# main_schematic_8.net
KiCad netlist of a schematic drawn in EAGLE
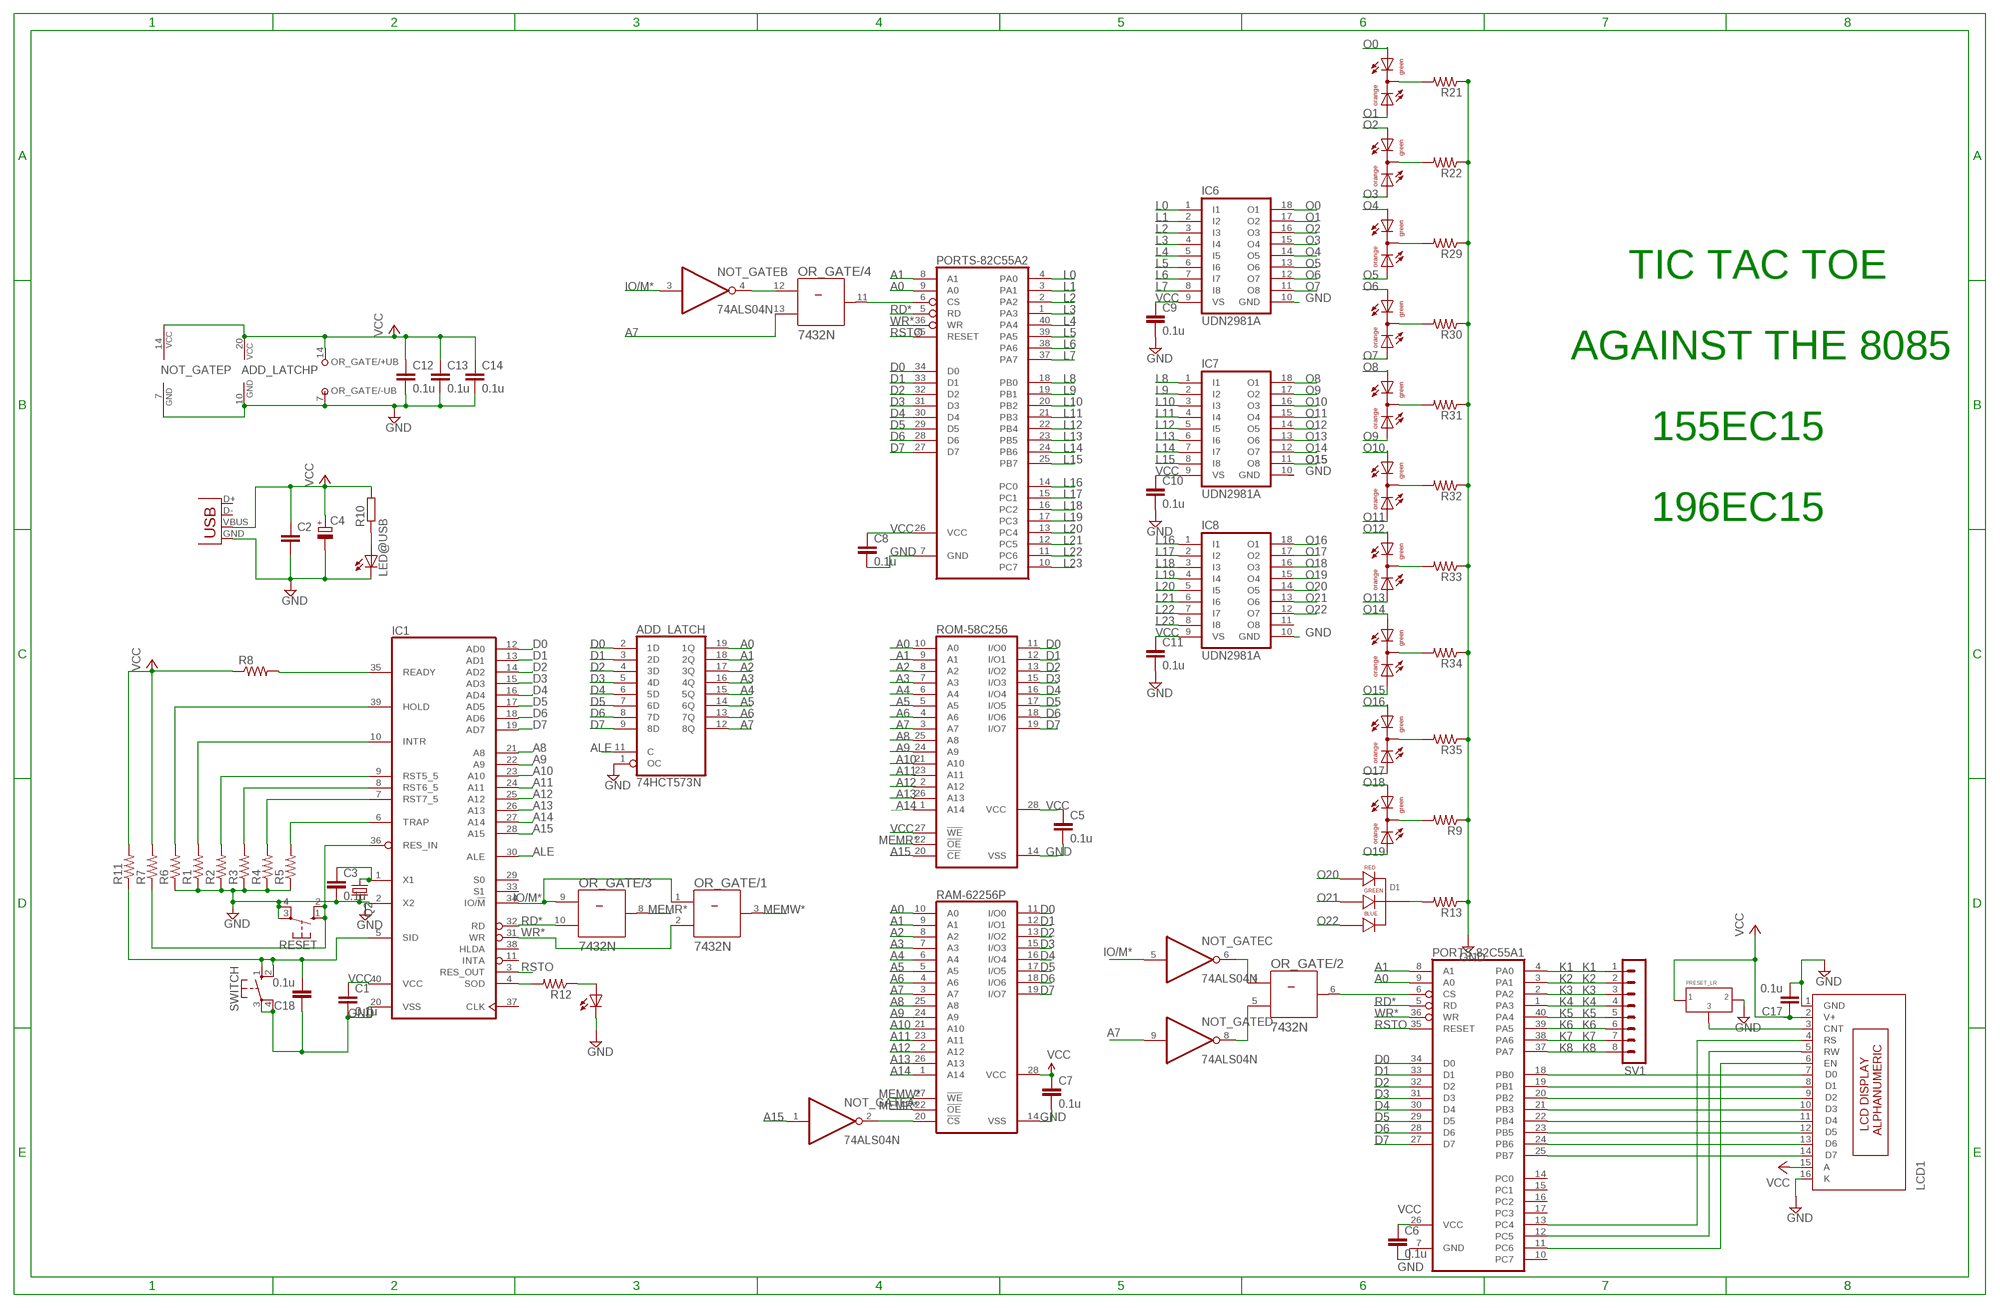
[diagram p0: schematic, sheet 1]

(export (version "E")
  (design (tool "Eeschema 10.0.6"))
  (components
    (comp (ref "ADD_LATCH")
      (value "74HCT573N")
      (footprint "eagle-import:DIL20")
      (libsource (lib "eagle-import") (part "74573NHCT"))
    )
    (comp (ref "C1")
      (value "0.1u")
      (footprint "eagle-import:C2.5-3")
      (libsource (lib "eagle-import") (part "capacitor-wima_116_C2,5-3"))
    )
    (comp (ref "C2")
      (value "C-EU025-024X044")
      (footprint "eagle-import:C025-024X044")
      (libsource (lib "eagle-import") (part "C-EU025-024X044"))
    )
    (comp (ref "C3")
      (value "0.1u")
      (footprint "eagle-import:C025-024X044")
      (libsource (lib "eagle-import") (part "C-EU025-024X044"))
    )
    (comp (ref "C4")
      (value "CPOL-EUE5-8.5")
      (footprint "eagle-import:E5-8,5")
      (libsource (lib "eagle-import") (part "CPOL-EUE5-8.5"))
    )
    (comp (ref "C5")
      (value "0.1u")
      (footprint "eagle-import:C025-024X044")
      (libsource (lib "eagle-import") (part "C-EU025-024X044"))
    )
    (comp (ref "C6")
      (value "0.1u")
      (footprint "eagle-import:C050-024X044")
      (libsource (lib "eagle-import") (part "resistor_C-EU050-024X044"))
    )
    (comp (ref "C7")
      (value "0.1u")
      (footprint "eagle-import:C025-024X044")
      (libsource (lib "eagle-import") (part "C-EU025-024X044"))
    )
    (comp (ref "C8")
      (value "0.1u")
      (footprint "eagle-import:C025-024X044")
      (libsource (lib "eagle-import") (part "C-EU025-024X044"))
    )
    (comp (ref "C9")
      (value "0.1u")
      (footprint "eagle-import:C025-024X044")
      (libsource (lib "eagle-import") (part "C-EU025-024X044"))
    )
    (comp (ref "C10")
      (value "0.1u")
      (footprint "eagle-import:C025-024X044")
      (libsource (lib "eagle-import") (part "C-EU025-024X044"))
    )
    (comp (ref "C11")
      (value "0.1u")
      (footprint "eagle-import:C025-024X044")
      (libsource (lib "eagle-import") (part "C-EU025-024X044"))
    )
    (comp (ref "C12")
      (value "0.1u")
      (footprint "eagle-import:C025-024X044")
      (libsource (lib "eagle-import") (part "C-EU025-024X044"))
    )
    (comp (ref "C13")
      (value "0.1u")
      (footprint "eagle-import:C025-024X044")
      (libsource (lib "eagle-import") (part "C-EU025-024X044"))
    )
    (comp (ref "C14")
      (value "0.1u")
      (footprint "eagle-import:C025-024X044")
      (libsource (lib "eagle-import") (part "C-EU025-024X044"))
    )
    (comp (ref "C17")
      (value "0.1u")
      (footprint "eagle-import:C025-024X044")
      (libsource (lib "eagle-import") (part "C-EU025-024X044"))
    )
    (comp (ref "C18")
      (value "0.1u")
      (footprint "eagle-import:C2.5-3")
      (libsource (lib "eagle-import") (part "C2,5-3"))
    )
    (comp (ref "D1")
      (value "LED-RGB-CC-THRUCLEAR")
      (footprint "eagle-import:LED-RGB-THRU")
      (libsource (lib "eagle-import") (part "LED-RGB-CC-THRUCLEAR"))
    )
    (comp (ref "IC1")
      (value "8085")
      (footprint "eagle-import:DIL40")
      (libsource (lib "eagle-import") (part "8085"))
    )
    (comp (ref "IC6")
      (value "UDN2981A")
      (footprint "eagle-import:DIL18")
      (libsource (lib "eagle-import") (part "UDN298A1"))
    )
    (comp (ref "IC7")
      (value "UDN2981A")
      (footprint "eagle-import:DIL18")
      (libsource (lib "eagle-import") (part "UDN298A1"))
    )
    (comp (ref "IC8")
      (value "UDN2981A")
      (footprint "eagle-import:DIL18")
      (libsource (lib "eagle-import") (part "UDN298A1"))
    )
    (comp (ref "LCD1")
      (value "16X2LCD")
      (footprint "eagle-import:16X2_LCD")
      (libsource (lib "eagle-import") (part "16X2LCD"))
    )
    (comp (ref "LED@SOD")
      (value "LED3MM")
      (footprint "eagle-import:LED3MM")
      (libsource (lib "eagle-import") (part "led_LED3MM"))
    )
    (comp (ref "LED@USB")
      (value "LED5MM")
      (footprint "eagle-import:LED5MM")
      (libsource (lib "eagle-import") (part "LED5MM"))
    )
    (comp (ref "LEDA")
      (value "TLUV5300")
      (footprint "eagle-import:TLUV5300")
      (libsource (lib "eagle-import") (part "TLUV5300"))
    )
    (comp (ref "LEDB")
      (value "TLUV5300")
      (footprint "eagle-import:TLUV5300")
      (libsource (lib "eagle-import") (part "TLUV5300"))
    )
    (comp (ref "LEDC")
      (value "TLUV5300")
      (footprint "eagle-import:TLUV5300")
      (libsource (lib "eagle-import") (part "TLUV5300"))
    )
    (comp (ref "LEDD")
      (value "TLUV5300")
      (footprint "eagle-import:TLUV5300")
      (libsource (lib "eagle-import") (part "TLUV5300"))
    )
    (comp (ref "LEDE")
      (value "TLUV5300")
      (footprint "eagle-import:TLUV5300")
      (libsource (lib "eagle-import") (part "TLUV5300"))
    )
    (comp (ref "LEDF")
      (value "TLUV5300")
      (footprint "eagle-import:TLUV5300")
      (libsource (lib "eagle-import") (part "TLUV5300"))
    )
    (comp (ref "LEDG")
      (value "TLUV5300")
      (footprint "eagle-import:TLUV5300")
      (libsource (lib "eagle-import") (part "TLUV5300"))
    )
    (comp (ref "LEDH")
      (value "TLUV5300")
      (footprint "eagle-import:TLUV5300")
      (libsource (lib "eagle-import") (part "TLUV5300"))
    )
    (comp (ref "LEDI")
      (value "TLUV5300")
      (footprint "eagle-import:TLUV5300")
      (libsource (lib "eagle-import") (part "TLUV5300"))
    )
    (comp (ref "LEDJ")
      (value "TLUV5300")
      (footprint "eagle-import:TLUV5300")
      (libsource (lib "eagle-import") (part "TLUV5300"))
    )
    (comp (ref "NOT_GATE")
      (value "74ALS04N")
      (footprint "eagle-import:DIL14")
      (libsource (lib "eagle-import") (part "7404NALS"))
    )
    (comp (ref "OR_GATE")
      (value "7432N")
      (footprint "eagle-import:DIL14")
      (fields (field (name "SPICEPREFIX") "J"))
      (libsource (lib "eagle-import") (part "7432N"))
    )
    (comp (ref "PORTS-82C55A1")
      (value "82C55A")
      (footprint "eagle-import:DIL40")
      (fields (field (name "MF") "INTERSIL") (field (name "MPN") "IP82C55AZ"))
      (libsource (lib "eagle-import") (part "82C55A"))
    )
    (comp (ref "PORTS-82C55A2")
      (value "82C55A")
      (footprint "eagle-import:DIL40")
      (fields (field (name "MF") "INTERSIL") (field (name "MPN") "IP82C55AZ"))
      (libsource (lib "eagle-import") (part "82C55A"))
    )
    (comp (ref "Q2")
      (value "CRYSTALHC49US")
      (footprint "eagle-import:HC49US")
      (libsource (lib "eagle-import") (part "CRYSTALHC49US"))
    )
    (comp (ref "R1")
      (value "R-US_0204/2V")
      (footprint "eagle-import:0204V")
      (libsource (lib "eagle-import") (part "R-US_0204/2V"))
    )
    (comp (ref "R2")
      (value "R-US_0204/2V")
      (footprint "eagle-import:0204V")
      (libsource (lib "eagle-import") (part "R-US_0204/2V"))
    )
    (comp (ref "R3")
      (value "R-US_0204/2V")
      (footprint "eagle-import:0204V")
      (libsource (lib "eagle-import") (part "R-US_0204/2V"))
    )
    (comp (ref "R4")
      (value "R-US_0204/2V")
      (footprint "eagle-import:0204V")
      (libsource (lib "eagle-import") (part "R-US_0204/2V"))
    )
    (comp (ref "R5")
      (value "R-US_0204/2V")
      (footprint "eagle-import:0204V")
      (libsource (lib "eagle-import") (part "R-US_0204/2V"))
    )
    (comp (ref "R6")
      (value "R-US_0204/2V")
      (footprint "eagle-import:0204V")
      (libsource (lib "eagle-import") (part "R-US_0204/2V"))
    )
    (comp (ref "R7")
      (value "R-US_0204/2V")
      (footprint "eagle-import:0204V")
      (libsource (lib "eagle-import") (part "R-US_0204/2V"))
    )
    (comp (ref "R8")
      (value "R-US_0204/2V")
      (footprint "eagle-import:0204V")
      (libsource (lib "eagle-import") (part "R-US_0204/2V"))
    )
    (comp (ref "R9")
      (value "R-US_0204/2V")
      (footprint "eagle-import:0204V")
      (libsource (lib "eagle-import") (part "R-US_0204/2V"))
    )
    (comp (ref "R10")
      (value "R-EU_0204/7")
      (footprint "eagle-import:0204_7")
      (libsource (lib "eagle-import") (part "R-EU_0204/7"))
    )
    (comp (ref "R11")
      (value "R-US_0204/2V")
      (footprint "eagle-import:0204V")
      (libsource (lib "eagle-import") (part "R-US_0204/2V"))
    )
    (comp (ref "R12")
      (value "R-US_0204/2V")
      (footprint "eagle-import:0204V")
      (libsource (lib "eagle-import") (part "R-US_0204/2V"))
    )
    (comp (ref "R13")
      (value "R-US_0204/2V")
      (footprint "eagle-import:0204V")
      (libsource (lib "eagle-import") (part "R-US_0204/2V"))
    )
    (comp (ref "R21")
      (value "R-US_0204/2V")
      (footprint "eagle-import:0204V")
      (libsource (lib "eagle-import") (part "R-US_0204/2V"))
    )
    (comp (ref "R22")
      (value "R-US_0204/2V")
      (footprint "eagle-import:0204V")
      (libsource (lib "eagle-import") (part "R-US_0204/2V"))
    )
    (comp (ref "R29")
      (value "R-US_0204/2V")
      (footprint "eagle-import:0204V")
      (libsource (lib "eagle-import") (part "R-US_0204/2V"))
    )
    (comp (ref "R30")
      (value "R-US_0204/2V")
      (footprint "eagle-import:0204V")
      (libsource (lib "eagle-import") (part "R-US_0204/2V"))
    )
    (comp (ref "R31")
      (value "R-US_0204/2V")
      (footprint "eagle-import:0204V")
      (libsource (lib "eagle-import") (part "R-US_0204/2V"))
    )
    (comp (ref "R32")
      (value "R-US_0204/2V")
      (footprint "eagle-import:0204V")
      (libsource (lib "eagle-import") (part "R-US_0204/2V"))
    )
    (comp (ref "R33")
      (value "R-US_0204/2V")
      (footprint "eagle-import:0204V")
      (libsource (lib "eagle-import") (part "R-US_0204/2V"))
    )
    (comp (ref "R34")
      (value "R-US_0204/2V")
      (footprint "eagle-import:0204V")
      (libsource (lib "eagle-import") (part "R-US_0204/2V"))
    )
    (comp (ref "R35")
      (value "R-US_0204/2V")
      (footprint "eagle-import:0204V")
      (libsource (lib "eagle-import") (part "R-US_0204/2V"))
    )
    (comp (ref "RAM-62256P")
      (value "62256P")
      (footprint "eagle-import:DIL28-6")
      (libsource (lib "eagle-import") (part "62256P"))
    )
    (comp (ref "RESET")
      (value "10-XX")
      (footprint "eagle-import:B3F-10XX")
      (libsource (lib "eagle-import") (part "10-XX"))
    )
    (comp (ref "ROM-58C256")
      (value "58C256P")
      (footprint "eagle-import:DIL28-6")
      (fields (field (name "MPN") "HN58C256AP85E"))
      (libsource (lib "eagle-import") (part "58C256P"))
    )
    (comp (ref "SV1")
      (value "MA08-1")
      (footprint "eagle-import:MA08-1")
      (libsource (lib "eagle-import") (part "MA08-1"))
    )
    (comp (ref "SWITCH")
      (value "10-XX")
      (footprint "eagle-import:B3F-10XX")
      (libsource (lib "eagle-import") (part "CEDTv69_10-XX"))
    )
    (comp (ref "U$2")
      (value "PRESET_LR")
      (footprint "eagle-import:PRESET_LR")
      (libsource (lib "eagle-import") (part "PRESET_LR"))
    )
    (comp (ref "X1")
      (value "USBSMD")
      (footprint "eagle-import:USB-MINIB")
      (libsource (lib "eagle-import") (part "USBSMD"))
    )
  )
  (nets
    (net (code "1") (name "/A0") (class "Default")
      (node (ref "ADD_LATCH") (pin "19") (pinfunction "1Q_19") (pintype "tri_state"))
      (node (ref "PORTS-82C55A1") (pin "9") (pinfunction "A0_9") (pintype "input"))
      (node (ref "PORTS-82C55A2") (pin "9") (pinfunction "A0_9") (pintype "input"))
      (node (ref "RAM-62256P") (pin "10") (pinfunction "A0_10") (pintype "input"))
      (node (ref "ROM-58C256") (pin "10") (pinfunction "A0_10") (pintype "input"))
    )
    (net (code "2") (name "/A1") (class "Default")
      (node (ref "ADD_LATCH") (pin "18") (pinfunction "2Q_18") (pintype "tri_state"))
      (node (ref "PORTS-82C55A1") (pin "8") (pinfunction "A1_8") (pintype "input"))
      (node (ref "PORTS-82C55A2") (pin "8") (pinfunction "A1_8") (pintype "input"))
      (node (ref "RAM-62256P") (pin "9") (pinfunction "A1_9") (pintype "input"))
      (node (ref "ROM-58C256") (pin "9") (pinfunction "A1_9") (pintype "input"))
    )
    (net (code "3") (name "/A2") (class "Default")
      (node (ref "ADD_LATCH") (pin "17") (pinfunction "3Q_17") (pintype "tri_state"))
      (node (ref "RAM-62256P") (pin "8") (pinfunction "A2_8") (pintype "input"))
      (node (ref "ROM-58C256") (pin "8") (pinfunction "A2_8") (pintype "input"))
    )
    (net (code "4") (name "/A3") (class "Default")
      (node (ref "ADD_LATCH") (pin "16") (pinfunction "4Q_16") (pintype "tri_state"))
      (node (ref "RAM-62256P") (pin "7") (pinfunction "A3_7") (pintype "input"))
      (node (ref "ROM-58C256") (pin "7") (pinfunction "A3_7") (pintype "input"))
    )
    (net (code "5") (name "/A4") (class "Default")
      (node (ref "ADD_LATCH") (pin "15") (pinfunction "5Q_15") (pintype "tri_state"))
      (node (ref "RAM-62256P") (pin "6") (pinfunction "A4_6") (pintype "input"))
      (node (ref "ROM-58C256") (pin "6") (pinfunction "A4_6") (pintype "input"))
    )
    (net (code "6") (name "/A5") (class "Default")
      (node (ref "ADD_LATCH") (pin "14") (pinfunction "6Q_14") (pintype "tri_state"))
      (node (ref "RAM-62256P") (pin "5") (pinfunction "A5_5") (pintype "input"))
      (node (ref "ROM-58C256") (pin "5") (pinfunction "A5_5") (pintype "input"))
    )
    (net (code "7") (name "/A6") (class "Default")
      (node (ref "ADD_LATCH") (pin "13") (pinfunction "7Q_13") (pintype "tri_state"))
      (node (ref "RAM-62256P") (pin "4") (pinfunction "A6_4") (pintype "input"))
      (node (ref "ROM-58C256") (pin "4") (pinfunction "A6_4") (pintype "input"))
    )
    (net (code "8") (name "/A7") (class "Default")
      (node (ref "ADD_LATCH") (pin "12") (pinfunction "8Q_12") (pintype "tri_state"))
      (node (ref "NOT_GATE") (pin "9") (pinfunction "I_9") (pintype "input"))
      (node (ref "OR_GATE") (pin "13") (pinfunction "B_13") (pintype "input"))
      (node (ref "RAM-62256P") (pin "3") (pinfunction "A7_3") (pintype "input"))
      (node (ref "ROM-58C256") (pin "3") (pinfunction "A7_3") (pintype "input"))
    )
    (net (code "9") (name "/A8") (class "Default")
      (node (ref "IC1") (pin "21") (pinfunction "A8_21") (pintype "output"))
      (node (ref "RAM-62256P") (pin "25") (pinfunction "A8_25") (pintype "input"))
      (node (ref "ROM-58C256") (pin "25") (pinfunction "A8_25") (pintype "input"))
    )
    (net (code "10") (name "/A9") (class "Default")
      (node (ref "IC1") (pin "22") (pinfunction "A9_22") (pintype "output"))
      (node (ref "RAM-62256P") (pin "24") (pinfunction "A9_24") (pintype "input"))
      (node (ref "ROM-58C256") (pin "24") (pinfunction "A9_24") (pintype "input"))
    )
    (net (code "11") (name "/A10") (class "Default")
      (node (ref "IC1") (pin "23") (pinfunction "A10_23") (pintype "output"))
      (node (ref "RAM-62256P") (pin "21") (pinfunction "A10_21") (pintype "input"))
      (node (ref "ROM-58C256") (pin "21") (pinfunction "A10_21") (pintype "input"))
    )
    (net (code "12") (name "/A11") (class "Default")
      (node (ref "IC1") (pin "24") (pinfunction "A11_24") (pintype "output"))
      (node (ref "RAM-62256P") (pin "23") (pinfunction "A11_23") (pintype "input"))
      (node (ref "ROM-58C256") (pin "23") (pinfunction "A11_23") (pintype "input"))
    )
    (net (code "13") (name "/A12") (class "Default")
      (node (ref "IC1") (pin "25") (pinfunction "A12_25") (pintype "output"))
      (node (ref "RAM-62256P") (pin "2") (pinfunction "A12_2") (pintype "input"))
      (node (ref "ROM-58C256") (pin "2") (pinfunction "A12_2") (pintype "input"))
    )
    (net (code "14") (name "/A13") (class "Default")
      (node (ref "IC1") (pin "26") (pinfunction "A13_26") (pintype "output"))
      (node (ref "RAM-62256P") (pin "26") (pinfunction "A13_26") (pintype "input"))
      (node (ref "ROM-58C256") (pin "26") (pinfunction "A13_26") (pintype "input"))
    )
    (net (code "15") (name "/A14") (class "Default")
      (node (ref "IC1") (pin "27") (pinfunction "A14_27") (pintype "output"))
      (node (ref "RAM-62256P") (pin "1") (pinfunction "A14_1") (pintype "input"))
      (node (ref "ROM-58C256") (pin "1") (pinfunction "A14_1") (pintype "input"))
    )
    (net (code "16") (name "/A15") (class "Default")
      (node (ref "IC1") (pin "28") (pinfunction "A15_28") (pintype "output"))
      (node (ref "NOT_GATE") (pin "1") (pinfunction "I_1") (pintype "input"))
      (node (ref "ROM-58C256") (pin "20") (pinfunction "~{CE}_20") (pintype "input"))
    )
    (net (code "17") (name "/ALE") (class "Default")
      (node (ref "ADD_LATCH") (pin "11") (pinfunction "C_11") (pintype "input"))
      (node (ref "IC1") (pin "30") (pinfunction "ALE_30") (pintype "output"))
    )
    (net (code "18") (name "/D0") (class "Default")
      (node (ref "ADD_LATCH") (pin "2") (pinfunction "1D_2") (pintype "input"))
      (node (ref "IC1") (pin "12") (pinfunction "AD0_12") (pintype "bidirectional"))
      (node (ref "PORTS-82C55A1") (pin "34") (pinfunction "D0_34") (pintype "bidirectional"))
      (node (ref "PORTS-82C55A2") (pin "34") (pinfunction "D0_34") (pintype "bidirectional"))
      (node (ref "RAM-62256P") (pin "11") (pinfunction "I/O0_11") (pintype "bidirectional"))
      (node (ref "ROM-58C256") (pin "11") (pinfunction "I/O0_11") (pintype "tri_state"))
    )
    (net (code "19") (name "/D1") (class "Default")
      (node (ref "ADD_LATCH") (pin "3") (pinfunction "2D_3") (pintype "input"))
      (node (ref "IC1") (pin "13") (pinfunction "AD1_13") (pintype "bidirectional"))
      (node (ref "PORTS-82C55A1") (pin "33") (pinfunction "D1_33") (pintype "bidirectional"))
      (node (ref "PORTS-82C55A2") (pin "33") (pinfunction "D1_33") (pintype "bidirectional"))
      (node (ref "RAM-62256P") (pin "12") (pinfunction "I/O1_12") (pintype "bidirectional"))
      (node (ref "ROM-58C256") (pin "12") (pinfunction "I/O1_12") (pintype "tri_state"))
    )
    (net (code "20") (name "/D2") (class "Default")
      (node (ref "ADD_LATCH") (pin "4") (pinfunction "3D_4") (pintype "input"))
      (node (ref "IC1") (pin "14") (pinfunction "AD2_14") (pintype "bidirectional"))
      (node (ref "PORTS-82C55A1") (pin "32") (pinfunction "D2_32") (pintype "bidirectional"))
      (node (ref "PORTS-82C55A2") (pin "32") (pinfunction "D2_32") (pintype "bidirectional"))
      (node (ref "RAM-62256P") (pin "13") (pinfunction "I/O2_13") (pintype "bidirectional"))
      (node (ref "ROM-58C256") (pin "13") (pinfunction "I/O2_13") (pintype "tri_state"))
    )
    (net (code "21") (name "/D3") (class "Default")
      (node (ref "ADD_LATCH") (pin "5") (pinfunction "4D_5") (pintype "input"))
      (node (ref "IC1") (pin "15") (pinfunction "AD3_15") (pintype "bidirectional"))
      (node (ref "PORTS-82C55A1") (pin "31") (pinfunction "D3_31") (pintype "bidirectional"))
      (node (ref "PORTS-82C55A2") (pin "31") (pinfunction "D3_31") (pintype "bidirectional"))
      (node (ref "RAM-62256P") (pin "15") (pinfunction "I/O3_15") (pintype "bidirectional"))
      (node (ref "ROM-58C256") (pin "15") (pinfunction "I/O3_15") (pintype "tri_state"))
    )
    (net (code "22") (name "/D4") (class "Default")
      (node (ref "ADD_LATCH") (pin "6") (pinfunction "5D_6") (pintype "input"))
      (node (ref "IC1") (pin "16") (pinfunction "AD4_16") (pintype "bidirectional"))
      (node (ref "PORTS-82C55A1") (pin "30") (pinfunction "D4_30") (pintype "bidirectional"))
      (node (ref "PORTS-82C55A2") (pin "30") (pinfunction "D4_30") (pintype "bidirectional"))
      (node (ref "RAM-62256P") (pin "16") (pinfunction "I/O4_16") (pintype "bidirectional"))
      (node (ref "ROM-58C256") (pin "16") (pinfunction "I/O4_16") (pintype "tri_state"))
    )
    (net (code "23") (name "/D5") (class "Default")
      (node (ref "ADD_LATCH") (pin "7") (pinfunction "6D_7") (pintype "input"))
      (node (ref "IC1") (pin "17") (pinfunction "AD5_17") (pintype "bidirectional"))
      (node (ref "PORTS-82C55A1") (pin "29") (pinfunction "D5_29") (pintype "bidirectional"))
      (node (ref "PORTS-82C55A2") (pin "29") (pinfunction "D5_29") (pintype "bidirectional"))
      (node (ref "RAM-62256P") (pin "17") (pinfunction "I/O5_17") (pintype "bidirectional"))
      (node (ref "ROM-58C256") (pin "17") (pinfunction "I/O5_17") (pintype "tri_state"))
    )
    (net (code "24") (name "/D6") (class "Default")
      (node (ref "ADD_LATCH") (pin "8") (pinfunction "7D_8") (pintype "input"))
      (node (ref "IC1") (pin "18") (pinfunction "AD6_18") (pintype "bidirectional"))
      (node (ref "PORTS-82C55A1") (pin "28") (pinfunction "D6_28") (pintype "bidirectional"))
      (node (ref "PORTS-82C55A2") (pin "28") (pinfunction "D6_28") (pintype "bidirectional"))
      (node (ref "RAM-62256P") (pin "18") (pinfunction "I/O6_18") (pintype "bidirectional"))
      (node (ref "ROM-58C256") (pin "18") (pinfunction "I/O6_18") (pintype "tri_state"))
    )
    (net (code "25") (name "/D7") (class "Default")
      (node (ref "ADD_LATCH") (pin "9") (pinfunction "8D_9") (pintype "input"))
      (node (ref "IC1") (pin "19") (pinfunction "AD7_19") (pintype "bidirectional"))
      (node (ref "PORTS-82C55A1") (pin "27") (pinfunction "D7_27") (pintype "bidirectional"))
      (node (ref "PORTS-82C55A2") (pin "27") (pinfunction "D7_27") (pintype "bidirectional"))
      (node (ref "RAM-62256P") (pin "19") (pinfunction "I/O7_19") (pintype "bidirectional"))
      (node (ref "ROM-58C256") (pin "19") (pinfunction "I/O7_19") (pintype "tri_state"))
    )
    (net (code "26") (name "/IO{slash}M*") (class "Default")
      (node (ref "IC1") (pin "34") (pinfunction "IO/~{M}_34") (pintype "output"))
      (node (ref "NOT_GATE") (pin "3") (pinfunction "I_3") (pintype "input"))
      (node (ref "NOT_GATE") (pin "5") (pinfunction "I_5") (pintype "input"))
      (node (ref "OR_GATE") (pin "1") (pinfunction "A_1") (pintype "input"))
      (node (ref "OR_GATE") (pin "9") (pinfunction "A_9") (pintype "input"))
    )
    (net (code "27") (name "/K1") (class "Default")
      (node (ref "PORTS-82C55A1") (pin "4") (pinfunction "PA0_4") (pintype "bidirectional"))
      (node (ref "SV1") (pin "1") (pinfunction "1_1") (pintype "passive"))
    )
    (net (code "28") (name "/K2") (class "Default")
      (node (ref "PORTS-82C55A1") (pin "3") (pinfunction "PA1_3") (pintype "bidirectional"))
      (node (ref "SV1") (pin "2") (pinfunction "2_2") (pintype "passive"))
    )
    (net (code "29") (name "/K3") (class "Default")
      (node (ref "PORTS-82C55A1") (pin "2") (pinfunction "PA2_2") (pintype "bidirectional"))
      (node (ref "SV1") (pin "3") (pinfunction "3_3") (pintype "passive"))
    )
    (net (code "30") (name "/K4") (class "Default")
      (node (ref "PORTS-82C55A1") (pin "1") (pinfunction "PA3_1") (pintype "bidirectional"))
      (node (ref "SV1") (pin "4") (pinfunction "4_4") (pintype "passive"))
    )
    (net (code "31") (name "/K5") (class "Default")
      (node (ref "PORTS-82C55A1") (pin "40") (pinfunction "PA4_40") (pintype "bidirectional"))
      (node (ref "SV1") (pin "5") (pinfunction "5_5") (pintype "passive"))
    )
    (net (code "32") (name "/K6") (class "Default")
      (node (ref "PORTS-82C55A1") (pin "39") (pinfunction "PA5_39") (pintype "bidirectional"))
      (node (ref "SV1") (pin "6") (pinfunction "6_6") (pintype "passive"))
    )
    (net (code "33") (name "/K7") (class "Default")
      (node (ref "PORTS-82C55A1") (pin "38") (pinfunction "PA6_38") (pintype "bidirectional"))
      (node (ref "SV1") (pin "7") (pinfunction "7_7") (pintype "passive"))
    )
    (net (code "34") (name "/K8") (class "Default")
      (node (ref "PORTS-82C55A1") (pin "37") (pinfunction "PA7_37") (pintype "bidirectional"))
      (node (ref "SV1") (pin "8") (pinfunction "8_8") (pintype "passive"))
    )
    (net (code "35") (name "/L0") (class "Default")
      (node (ref "IC6") (pin "1") (pinfunction "I1_1") (pintype "input"))
      (node (ref "PORTS-82C55A2") (pin "4") (pinfunction "PA0_4") (pintype "bidirectional"))
    )
    (net (code "36") (name "/L1") (class "Default")
      (node (ref "IC6") (pin "2") (pinfunction "I2_2") (pintype "input"))
      (node (ref "PORTS-82C55A2") (pin "3") (pinfunction "PA1_3") (pintype "bidirectional"))
    )
    (net (code "37") (name "/L2") (class "Default")
      (node (ref "IC6") (pin "3") (pinfunction "I3_3") (pintype "input"))
      (node (ref "PORTS-82C55A2") (pin "2") (pinfunction "PA2_2") (pintype "bidirectional"))
    )
    (net (code "38") (name "/L3") (class "Default")
      (node (ref "IC6") (pin "4") (pinfunction "I4_4") (pintype "input"))
      (node (ref "PORTS-82C55A2") (pin "1") (pinfunction "PA3_1") (pintype "bidirectional"))
    )
    (net (code "39") (name "/L4") (class "Default")
      (node (ref "IC6") (pin "5") (pinfunction "I5_5") (pintype "input"))
      (node (ref "PORTS-82C55A2") (pin "40") (pinfunction "PA4_40") (pintype "bidirectional"))
    )
    (net (code "40") (name "/L5") (class "Default")
      (node (ref "IC6") (pin "6") (pinfunction "I6_6") (pintype "input"))
      (node (ref "PORTS-82C55A2") (pin "39") (pinfunction "PA5_39") (pintype "bidirectional"))
    )
    (net (code "41") (name "/L6") (class "Default")
      (node (ref "IC6") (pin "7") (pinfunction "I7_7") (pintype "input"))
      (node (ref "PORTS-82C55A2") (pin "38") (pinfunction "PA6_38") (pintype "bidirectional"))
    )
    (net (code "42") (name "/L7") (class "Default")
      (node (ref "IC6") (pin "8") (pinfunction "I8_8") (pintype "input"))
      (node (ref "PORTS-82C55A2") (pin "37") (pinfunction "PA7_37") (pintype "bidirectional"))
    )
    (net (code "43") (name "/L8") (class "Default")
      (node (ref "IC7") (pin "1") (pinfunction "I1_1") (pintype "input"))
      (node (ref "PORTS-82C55A2") (pin "18") (pinfunction "PB0_18") (pintype "bidirectional"))
    )
    (net (code "44") (name "/L9") (class "Default")
      (node (ref "IC7") (pin "2") (pinfunction "I2_2") (pintype "input"))
      (node (ref "PORTS-82C55A2") (pin "19") (pinfunction "PB1_19") (pintype "bidirectional"))
    )
    (net (code "45") (name "/L10") (class "Default")
      (node (ref "IC7") (pin "3") (pinfunction "I3_3") (pintype "input"))
      (node (ref "PORTS-82C55A2") (pin "20") (pinfunction "PB2_20") (pintype "bidirectional"))
    )
    (net (code "46") (name "/L11") (class "Default")
      (node (ref "IC7") (pin "4") (pinfunction "I4_4") (pintype "input"))
      (node (ref "PORTS-82C55A2") (pin "21") (pinfunction "PB3_21") (pintype "bidirectional"))
    )
    (net (code "47") (name "/L12") (class "Default")
      (node (ref "IC7") (pin "5") (pinfunction "I5_5") (pintype "input"))
      (node (ref "PORTS-82C55A2") (pin "22") (pinfunction "PB4_22") (pintype "bidirectional"))
    )
    (net (code "48") (name "/L13") (class "Default")
      (node (ref "IC7") (pin "6") (pinfunction "I6_6") (pintype "input"))
      (node (ref "PORTS-82C55A2") (pin "23") (pinfunction "PB5_23") (pintype "bidirectional"))
    )
    (net (code "49") (name "/L14") (class "Default")
      (node (ref "IC7") (pin "7") (pinfunction "I7_7") (pintype "input"))
      (node (ref "PORTS-82C55A2") (pin "24") (pinfunction "PB6_24") (pintype "bidirectional"))
    )
    (net (code "50") (name "/L15") (class "Default")
      (node (ref "IC7") (pin "8") (pinfunction "I8_8") (pintype "input"))
      (node (ref "PORTS-82C55A2") (pin "25") (pinfunction "PB7_25") (pintype "bidirectional"))
    )
    (net (code "51") (name "/L16") (class "Default")
      (node (ref "IC8") (pin "1") (pinfunction "I1_1") (pintype "input"))
      (node (ref "PORTS-82C55A2") (pin "14") (pinfunction "PC0_14") (pintype "bidirectional"))
    )
    (net (code "52") (name "/L17") (class "Default")
      (node (ref "IC8") (pin "2") (pinfunction "I2_2") (pintype "input"))
      (node (ref "PORTS-82C55A2") (pin "15") (pinfunction "PC1_15") (pintype "bidirectional"))
    )
    (net (code "53") (name "/L18") (class "Default")
      (node (ref "IC8") (pin "3") (pinfunction "I3_3") (pintype "input"))
      (node (ref "PORTS-82C55A2") (pin "16") (pinfunction "PC2_16") (pintype "bidirectional"))
    )
    (net (code "54") (name "/L19") (class "Default")
      (node (ref "IC8") (pin "4") (pinfunction "I4_4") (pintype "input"))
      (node (ref "PORTS-82C55A2") (pin "17") (pinfunction "PC3_17") (pintype "bidirectional"))
    )
    (net (code "55") (name "/L20") (class "Default")
      (node (ref "IC8") (pin "5") (pinfunction "I5_5") (pintype "input"))
      (node (ref "PORTS-82C55A2") (pin "13") (pinfunction "PC4_13") (pintype "bidirectional"))
    )
    (net (code "56") (name "/L21") (class "Default")
      (node (ref "IC8") (pin "6") (pinfunction "I6_6") (pintype "input"))
      (node (ref "PORTS-82C55A2") (pin "12") (pinfunction "PC5_12") (pintype "bidirectional"))
    )
    (net (code "57") (name "/L22") (class "Default")
      (node (ref "IC8") (pin "7") (pinfunction "I7_7") (pintype "input"))
      (node (ref "PORTS-82C55A2") (pin "11") (pinfunction "PC6_11") (pintype "bidirectional"))
    )
    (net (code "58") (name "/L23") (class "Default")
      (node (ref "IC8") (pin "8") (pinfunction "I8_8") (pintype "input"))
      (node (ref "PORTS-82C55A2") (pin "10") (pinfunction "PC7_10") (pintype "bidirectional"))
    )
    (net (code "59") (name "/MEMR*") (class "Default")
      (node (ref "OR_GATE") (pin "8") (pinfunction "Y_8") (pintype "output"))
      (node (ref "RAM-62256P") (pin "22") (pinfunction "~{OE}_22") (pintype "input"))
      (node (ref "ROM-58C256") (pin "22") (pinfunction "~{OE}_22") (pintype "input"))
    )
    (net (code "60") (name "/MEMW*") (class "Default")
      (node (ref "OR_GATE") (pin "3") (pinfunction "Y_3") (pintype "output"))
      (node (ref "RAM-62256P") (pin "27") (pinfunction "~{WE}_27") (pintype "input"))
    )
    (net (code "61") (name "/O0") (class "Default")
      (node (ref "IC6") (pin "18") (pinfunction "O1_18") (pintype "open_collector"))
      (node (ref "LEDA") (pin "AG") (pinfunction "AG_AG") (pintype "passive"))
    )
    (net (code "62") (name "/O1") (class "Default")
      (node (ref "IC6") (pin "17") (pinfunction "O2_17") (pintype "open_collector"))
      (node (ref "LEDA") (pin "AO") (pinfunction "AO_AO") (pintype "passive"))
    )
    (net (code "63") (name "/O2") (class "Default")
      (node (ref "IC6") (pin "16") (pinfunction "O3_16") (pintype "open_collector"))
      (node (ref "LEDB") (pin "AG") (pinfunction "AG_AG") (pintype "passive"))
    )
    (net (code "64") (name "/O3") (class "Default")
      (node (ref "IC6") (pin "15") (pinfunction "O4_15") (pintype "open_collector"))
      (node (ref "LEDB") (pin "AO") (pinfunction "AO_AO") (pintype "passive"))
    )
    (net (code "65") (name "/O4") (class "Default")
      (node (ref "IC6") (pin "14") (pinfunction "O5_14") (pintype "open_collector"))
      (node (ref "LEDC") (pin "AG") (pinfunction "AG_AG") (pintype "passive"))
    )
    (net (code "66") (name "/O5") (class "Default")
      (node (ref "IC6") (pin "13") (pinfunction "O6_13") (pintype "open_collector"))
      (node (ref "LEDC") (pin "AO") (pinfunction "AO_AO") (pintype "passive"))
    )
    (net (code "67") (name "/O6") (class "Default")
      (node (ref "IC6") (pin "12") (pinfunction "O7_12") (pintype "open_collector"))
      (node (ref "LEDD") (pin "AG") (pinfunction "AG_AG") (pintype "passive"))
    )
    (net (code "68") (name "/O7") (class "Default")
      (node (ref "IC6") (pin "11") (pinfunction "O8_11") (pintype "open_collector"))
      (node (ref "LEDD") (pin "AO") (pinfunction "AO_AO") (pintype "passive"))
    )
    (net (code "69") (name "/O8") (class "Default")
      (node (ref "IC7") (pin "18") (pinfunction "O1_18") (pintype "open_collector"))
      (node (ref "LEDE") (pin "AG") (pinfunction "AG_AG") (pintype "passive"))
    )
    (net (code "70") (name "/O9") (class "Default")
      (node (ref "IC7") (pin "17") (pinfunction "O2_17") (pintype "open_collector"))
      (node (ref "LEDE") (pin "AO") (pinfunction "AO_AO") (pintype "passive"))
    )
    (net (code "71") (name "/O10") (class "Default")
      (node (ref "IC7") (pin "16") (pinfunction "O3_16") (pintype "open_collector"))
      (node (ref "LEDF") (pin "AG") (pinfunction "AG_AG") (pintype "passive"))
    )
    (net (code "72") (name "/O11") (class "Default")
      (node (ref "IC7") (pin "15") (pinfunction "O4_15") (pintype "open_collector"))
      (node (ref "LEDF") (pin "AO") (pinfunction "AO_AO") (pintype "passive"))
    )
    (net (code "73") (name "/O12") (class "Default")
      (node (ref "IC7") (pin "14") (pinfunction "O5_14") (pintype "open_collector"))
      (node (ref "LEDG") (pin "AG") (pinfunction "AG_AG") (pintype "passive"))
    )
    (net (code "74") (name "/O13") (class "Default")
      (node (ref "IC7") (pin "13") (pinfunction "O6_13") (pintype "open_collector"))
      (node (ref "LEDG") (pin "AO") (pinfunction "AO_AO") (pintype "passive"))
    )
    (net (code "75") (name "/O14") (class "Default")
      (node (ref "IC7") (pin "12") (pinfunction "O7_12") (pintype "open_collector"))
      (node (ref "LEDH") (pin "AG") (pinfunction "AG_AG") (pintype "passive"))
    )
    (net (code "76") (name "/O15") (class "Default")
      (node (ref "IC7") (pin "11") (pinfunction "O8_11") (pintype "open_collector"))
      (node (ref "LEDH") (pin "AO") (pinfunction "AO_AO") (pintype "passive"))
    )
    (net (code "77") (name "/O16") (class "Default")
      (node (ref "IC8") (pin "18") (pinfunction "O1_18") (pintype "open_collector"))
      (node (ref "LEDI") (pin "AG") (pinfunction "AG_AG") (pintype "passive"))
    )
    (net (code "78") (name "/O17") (class "Default")
      (node (ref "IC8") (pin "17") (pinfunction "O2_17") (pintype "open_collector"))
      (node (ref "LEDI") (pin "AO") (pinfunction "AO_AO") (pintype "passive"))
    )
    (net (code "79") (name "/O18") (class "Default")
      (node (ref "IC8") (pin "16") (pinfunction "O3_16") (pintype "open_collector"))
      (node (ref "LEDJ") (pin "AG") (pinfunction "AG_AG") (pintype "passive"))
    )
    (net (code "80") (name "/O19") (class "Default")
      (node (ref "IC8") (pin "15") (pinfunction "O4_15") (pintype "open_collector"))
      (node (ref "LEDJ") (pin "AO") (pinfunction "AO_AO") (pintype "passive"))
    )
    (net (code "81") (name "/O20") (class "Default")
      (node (ref "D1") (pin "1") (pinfunction "RED_CATHODE_1") (pintype "bidirectional"))
      (node (ref "IC8") (pin "14") (pinfunction "O5_14") (pintype "open_collector"))
    )
    (net (code "82") (name "/O21") (class "Default")
      (node (ref "D1") (pin "3") (pinfunction "GREEN_CATHODE_3") (pintype "bidirectional"))
      (node (ref "IC8") (pin "13") (pinfunction "O6_13") (pintype "open_collector"))
    )
    (net (code "83") (name "/O22") (class "Default")
      (node (ref "D1") (pin "4") (pinfunction "BLUE_CATHODE_4") (pintype "bidirectional"))
      (node (ref "IC8") (pin "12") (pinfunction "O7_12") (pintype "open_collector"))
    )
    (net (code "84") (name "/RD*") (class "Default")
      (node (ref "IC1") (pin "32") (pinfunction "RD_32") (pintype "output"))
      (node (ref "OR_GATE") (pin "10") (pinfunction "B_10") (pintype "input"))
      (node (ref "PORTS-82C55A1") (pin "5") (pinfunction "RD_5") (pintype "input"))
      (node (ref "PORTS-82C55A2") (pin "5") (pinfunction "RD_5") (pintype "input"))
    )
    (net (code "85") (name "/RSTO") (class "Default")
      (node (ref "IC1") (pin "3") (pinfunction "RES_OUT_3") (pintype "output"))
      (node (ref "PORTS-82C55A1") (pin "35") (pinfunction "RESET_35") (pintype "input"))
      (node (ref "PORTS-82C55A2") (pin "35") (pinfunction "RESET_35") (pintype "input"))
    )
    (net (code "86") (name "/WR*") (class "Default")
      (node (ref "IC1") (pin "31") (pinfunction "WR_31") (pintype "output"))
      (node (ref "OR_GATE") (pin "2") (pinfunction "B_2") (pintype "input"))
      (node (ref "PORTS-82C55A1") (pin "36") (pinfunction "WR_36") (pintype "input"))
      (node (ref "PORTS-82C55A2") (pin "36") (pinfunction "WR_36") (pintype "input"))
    )
    (net (code "87") (name "GND") (class "Default")
      (node (ref "ADD_LATCH") (pin "1") (pinfunction "OC_1") (pintype "input"))
      (node (ref "ADD_LATCH") (pin "10") (pinfunction "GND_10") (pintype "power_in"))
      (node (ref "C1") (pin "2") (pinfunction "2_2") (pintype "passive"))
      (node (ref "C10") (pin "2") (pinfunction "2_2") (pintype "passive"))
      (node (ref "C11") (pin "2") (pinfunction "2_2") (pintype "passive"))
      (node (ref "C12") (pin "2") (pinfunction "2_2") (pintype "passive"))
      (node (ref "C13") (pin "2") (pinfunction "2_2") (pintype "passive"))
      (node (ref "C14") (pin "2") (pinfunction "2_2") (pintype "passive"))
      (node (ref "C17") (pin "2") (pinfunction "2_2") (pintype "passive"))
      (node (ref "C18") (pin "1") (pinfunction "1_1") (pintype "passive"))
      (node (ref "C2") (pin "2") (pinfunction "2_2") (pintype "passive"))
      (node (ref "C3") (pin "2") (pinfunction "2_2") (pintype "passive"))
      (node (ref "C4") (pin "-") (pinfunction "-_-") (pintype "passive"))
      (node (ref "C5") (pin "2") (pinfunction "2_2") (pintype "passive"))
      (node (ref "C6") (pin "2") (pinfunction "2_2") (pintype "passive"))
      (node (ref "C7") (pin "2") (pinfunction "2_2") (pintype "passive"))
      (node (ref "C8") (pin "2") (pinfunction "2_2") (pintype "passive"))
      (node (ref "C9") (pin "2") (pinfunction "2_2") (pintype "passive"))
      (node (ref "IC1") (pin "2") (pinfunction "X2_2") (pintype "input"))
      (node (ref "IC1") (pin "20") (pinfunction "VSS_20") (pintype "power_in"))
      (node (ref "IC6") (pin "10") (pinfunction "GND_10") (pintype "power_in"))
      (node (ref "IC7") (pin "10") (pinfunction "GND_10") (pintype "power_in"))
      (node (ref "IC8") (pin "10") (pinfunction "GND_10") (pintype "power_in"))
      (node (ref "LCD1") (pin "1") (pinfunction "GND_1") (pintype "bidirectional"))
      (node (ref "LCD1") (pin "16") (pinfunction "K_16") (pintype "bidirectional"))
      (node (ref "LED@SOD") (pin "K") (pinfunction "C_K") (pintype "passive"))
      (node (ref "LED@USB") (pin "K") (pinfunction "C_K") (pintype "passive"))
      (node (ref "NOT_GATE") (pin "7") (pinfunction "GND_7") (pintype "power_in"))
      (node (ref "OR_GATE") (pin "7") (pinfunction "-UB_7") (pintype "power_in"))
      (node (ref "PORTS-82C55A1") (pin "7") (pinfunction "GND_7") (pintype "power_in"))
      (node (ref "PORTS-82C55A2") (pin "7") (pinfunction "GND_7") (pintype "power_in"))
      (node (ref "Q2") (pin "2") (pinfunction "2_2") (pintype "passive"))
      (node (ref "R1") (pin "1") (pinfunction "1_1") (pintype "passive"))
      (node (ref "R13") (pin "1") (pinfunction "1_1") (pintype "passive"))
      (node (ref "R2") (pin "1") (pinfunction "1_1") (pintype "passive"))
      (node (ref "R21") (pin "1") (pinfunction "1_1") (pintype "passive"))
      (node (ref "R22") (pin "1") (pinfunction "1_1") (pintype "passive"))
      (node (ref "R29") (pin "1") (pinfunction "1_1") (pintype "passive"))
      (node (ref "R3") (pin "1") (pinfunction "1_1") (pintype "passive"))
      (node (ref "R30") (pin "1") (pinfunction "1_1") (pintype "passive"))
      (node (ref "R31") (pin "1") (pinfunction "1_1") (pintype "passive"))
      (node (ref "R32") (pin "1") (pinfunction "1_1") (pintype "passive"))
      (node (ref "R33") (pin "1") (pinfunction "1_1") (pintype "passive"))
      (node (ref "R34") (pin "1") (pinfunction "1_1") (pintype "passive"))
      (node (ref "R35") (pin "1") (pinfunction "1_1") (pintype "passive"))
      (node (ref "R4") (pin "1") (pinfunction "1_1") (pintype "passive"))
      (node (ref "R5") (pin "1") (pinfunction "1_1") (pintype "passive"))
      (node (ref "R6") (pin "1") (pinfunction "1_1") (pintype "passive"))
      (node (ref "R9") (pin "1") (pinfunction "1_1") (pintype "passive"))
      (node (ref "RAM-62256P") (pin "14") (pinfunction "VSS_14") (pintype "power_in"))
      (node (ref "RESET") (pin "3") (pinfunction "P_3") (pintype "passive"))
      (node (ref "RESET") (pin "4") (pinfunction "P1_4") (pintype "passive"))
      (node (ref "ROM-58C256") (pin "14") (pinfunction "VSS_14") (pintype "power_in"))
      (node (ref "SWITCH") (pin "3") (pinfunction "P_3") (pintype "passive"))
      (node (ref "SWITCH") (pin "4") (pinfunction "P1_4") (pintype "passive"))
      (node (ref "U$2") (pin "P$2") (pinfunction "2_P$2") (pintype "passive"))
      (node (ref "X1") (pin "GND") (pinfunction "GND_GND") (pintype "bidirectional"))
    )
    (net (code "88") (name "Net-(D1-CATHODE)") (class "Default")
      (node (ref "D1") (pin "2") (pinfunction "CATHODE_2") (pintype "bidirectional"))
      (node (ref "R13") (pin "2") (pinfunction "2_2") (pintype "passive"))
    )
    (net (code "89") (name "Net-(IC1-HOLD)") (class "Default")
      (node (ref "IC1") (pin "39") (pinfunction "HOLD_39") (pintype "input"))
      (node (ref "R6") (pin "2") (pinfunction "2_2") (pintype "passive"))
    )
    (net (code "90") (name "Net-(IC1-INTR)") (class "Default")
      (node (ref "IC1") (pin "10") (pinfunction "INTR_10") (pintype "input"))
      (node (ref "R1") (pin "2") (pinfunction "2_2") (pintype "passive"))
    )
    (net (code "91") (name "Net-(IC1-READY)") (class "Default")
      (node (ref "IC1") (pin "35") (pinfunction "READY_35") (pintype "input"))
      (node (ref "R8") (pin "2") (pinfunction "2_2") (pintype "passive"))
    )
    (net (code "92") (name "Net-(IC1-RES_IN)") (class "Default")
      (node (ref "IC1") (pin "36") (pinfunction "RES_IN_36") (pintype "input"))
      (node (ref "R7") (pin "1") (pinfunction "1_1") (pintype "passive"))
      (node (ref "RESET") (pin "1") (pinfunction "S_1") (pintype "passive"))
      (node (ref "RESET") (pin "2") (pinfunction "S1_2") (pintype "passive"))
    )
    (net (code "93") (name "Net-(IC1-RST5_5)") (class "Default")
      (node (ref "IC1") (pin "9") (pinfunction "RST5_5_9") (pintype "input"))
      (node (ref "R2") (pin "2") (pinfunction "2_2") (pintype "passive"))
    )
    (net (code "94") (name "Net-(IC1-RST6_5)") (class "Default")
      (node (ref "IC1") (pin "8") (pinfunction "RST6_5_8") (pintype "input"))
      (node (ref "R3") (pin "2") (pinfunction "2_2") (pintype "passive"))
    )
    (net (code "95") (name "Net-(IC1-RST7_5)") (class "Default")
      (node (ref "IC1") (pin "7") (pinfunction "RST7_5_7") (pintype "input"))
      (node (ref "R4") (pin "2") (pinfunction "2_2") (pintype "passive"))
    )
    (net (code "96") (name "Net-(IC1-SID)") (class "Default")
      (node (ref "C18") (pin "2") (pinfunction "2_2") (pintype "passive"))
      (node (ref "IC1") (pin "5") (pinfunction "SID_5") (pintype "input"))
      (node (ref "R11") (pin "1") (pinfunction "1_1") (pintype "passive"))
      (node (ref "SWITCH") (pin "1") (pinfunction "S_1") (pintype "passive"))
      (node (ref "SWITCH") (pin "2") (pinfunction "S1_2") (pintype "passive"))
    )
    (net (code "97") (name "Net-(IC1-SOD)") (class "Default")
      (node (ref "IC1") (pin "4") (pinfunction "SOD_4") (pintype "output"))
      (node (ref "R12") (pin "2") (pinfunction "2_2") (pintype "passive"))
    )
    (net (code "98") (name "Net-(IC1-TRAP)") (class "Default")
      (node (ref "IC1") (pin "6") (pinfunction "TRAP_6") (pintype "input"))
      (node (ref "R5") (pin "2") (pinfunction "2_2") (pintype "passive"))
    )
    (net (code "99") (name "Net-(IC1-X1)") (class "Default")
      (node (ref "C3") (pin "1") (pinfunction "1_1") (pintype "passive"))
      (node (ref "IC1") (pin "1") (pinfunction "X1_1") (pintype "input"))
      (node (ref "Q2") (pin "1") (pinfunction "1_1") (pintype "passive"))
    )
    (net (code "100") (name "Net-(LCD1-CNT)") (class "Default")
      (node (ref "LCD1") (pin "3") (pinfunction "CNT_3") (pintype "bidirectional"))
      (node (ref "U$2") (pin "P$3") (pinfunction "3_P$3") (pintype "passive"))
    )
    (net (code "101") (name "Net-(LCD1-D0)") (class "Default")
      (node (ref "LCD1") (pin "7") (pinfunction "D0_7") (pintype "bidirectional"))
      (node (ref "PORTS-82C55A1") (pin "18") (pinfunction "PB0_18") (pintype "bidirectional"))
    )
    (net (code "102") (name "Net-(LCD1-D1)") (class "Default")
      (node (ref "LCD1") (pin "8") (pinfunction "D1_8") (pintype "bidirectional"))
      (node (ref "PORTS-82C55A1") (pin "19") (pinfunction "PB1_19") (pintype "bidirectional"))
    )
    (net (code "103") (name "Net-(LCD1-D2)") (class "Default")
      (node (ref "LCD1") (pin "9") (pinfunction "D2_9") (pintype "bidirectional"))
      (node (ref "PORTS-82C55A1") (pin "20") (pinfunction "PB2_20") (pintype "bidirectional"))
    )
    (net (code "104") (name "Net-(LCD1-D3)") (class "Default")
      (node (ref "LCD1") (pin "10") (pinfunction "D3_10") (pintype "bidirectional"))
      (node (ref "PORTS-82C55A1") (pin "21") (pinfunction "PB3_21") (pintype "bidirectional"))
    )
    (net (code "105") (name "Net-(LCD1-D4)") (class "Default")
      (node (ref "LCD1") (pin "11") (pinfunction "D4_11") (pintype "bidirectional"))
      (node (ref "PORTS-82C55A1") (pin "22") (pinfunction "PB4_22") (pintype "bidirectional"))
    )
    (net (code "106") (name "Net-(LCD1-D5)") (class "Default")
      (node (ref "LCD1") (pin "12") (pinfunction "D5_12") (pintype "bidirectional"))
      (node (ref "PORTS-82C55A1") (pin "23") (pinfunction "PB5_23") (pintype "bidirectional"))
    )
    (net (code "107") (name "Net-(LCD1-D6)") (class "Default")
      (node (ref "LCD1") (pin "13") (pinfunction "D6_13") (pintype "bidirectional"))
      (node (ref "PORTS-82C55A1") (pin "24") (pinfunction "PB6_24") (pintype "bidirectional"))
    )
    (net (code "108") (name "Net-(LCD1-D7)") (class "Default")
      (node (ref "LCD1") (pin "14") (pinfunction "D7_14") (pintype "bidirectional"))
      (node (ref "PORTS-82C55A1") (pin "25") (pinfunction "PB7_25") (pintype "bidirectional"))
    )
    (net (code "109") (name "Net-(LCD1-EN)") (class "Default")
      (node (ref "LCD1") (pin "6") (pinfunction "EN_6") (pintype "bidirectional"))
      (node (ref "PORTS-82C55A1") (pin "11") (pinfunction "PC6_11") (pintype "bidirectional"))
    )
    (net (code "110") (name "Net-(LCD1-RS)") (class "Default")
      (node (ref "LCD1") (pin "4") (pinfunction "RS_4") (pintype "bidirectional"))
      (node (ref "PORTS-82C55A1") (pin "13") (pinfunction "PC4_13") (pintype "bidirectional"))
    )
    (net (code "111") (name "Net-(LCD1-RW)") (class "Default")
      (node (ref "LCD1") (pin "5") (pinfunction "RW_5") (pintype "bidirectional"))
      (node (ref "PORTS-82C55A1") (pin "12") (pinfunction "PC5_12") (pintype "bidirectional"))
    )
    (net (code "112") (name "Net-(LED@SOD-PadA)") (class "Default")
      (node (ref "LED@SOD") (pin "A") (pinfunction "A_A") (pintype "passive"))
      (node (ref "R12") (pin "1") (pinfunction "1_1") (pintype "passive"))
    )
    (net (code "113") (name "Net-(LED@USB-PadA)") (class "Default")
      (node (ref "LED@USB") (pin "A") (pinfunction "A_A") (pintype "passive"))
      (node (ref "R10") (pin "1") (pinfunction "1_1") (pintype "passive"))
    )
    (net (code "114") (name "Net-(LEDA-PadCC)") (class "Default")
      (node (ref "LEDA") (pin "CC") (pinfunction "CC_CC") (pintype "passive"))
      (node (ref "R21") (pin "2") (pinfunction "2_2") (pintype "passive"))
    )
    (net (code "115") (name "Net-(LEDB-PadCC)") (class "Default")
      (node (ref "LEDB") (pin "CC") (pinfunction "CC_CC") (pintype "passive"))
      (node (ref "R22") (pin "2") (pinfunction "2_2") (pintype "passive"))
    )
    (net (code "116") (name "Net-(LEDC-PadCC)") (class "Default")
      (node (ref "LEDC") (pin "CC") (pinfunction "CC_CC") (pintype "passive"))
      (node (ref "R29") (pin "2") (pinfunction "2_2") (pintype "passive"))
    )
    (net (code "117") (name "Net-(LEDD-PadCC)") (class "Default")
      (node (ref "LEDD") (pin "CC") (pinfunction "CC_CC") (pintype "passive"))
      (node (ref "R30") (pin "2") (pinfunction "2_2") (pintype "passive"))
    )
    (net (code "118") (name "Net-(LEDE-PadCC)") (class "Default")
      (node (ref "LEDE") (pin "CC") (pinfunction "CC_CC") (pintype "passive"))
      (node (ref "R31") (pin "2") (pinfunction "2_2") (pintype "passive"))
    )
    (net (code "119") (name "Net-(LEDF-PadCC)") (class "Default")
      (node (ref "LEDF") (pin "CC") (pinfunction "CC_CC") (pintype "passive"))
      (node (ref "R32") (pin "2") (pinfunction "2_2") (pintype "passive"))
    )
    (net (code "120") (name "Net-(LEDG-PadCC)") (class "Default")
      (node (ref "LEDG") (pin "CC") (pinfunction "CC_CC") (pintype "passive"))
      (node (ref "R33") (pin "2") (pinfunction "2_2") (pintype "passive"))
    )
    (net (code "121") (name "Net-(LEDH-PadCC)") (class "Default")
      (node (ref "LEDH") (pin "CC") (pinfunction "CC_CC") (pintype "passive"))
      (node (ref "R34") (pin "2") (pinfunction "2_2") (pintype "passive"))
    )
    (net (code "122") (name "Net-(LEDI-PadCC)") (class "Default")
      (node (ref "LEDI") (pin "CC") (pinfunction "CC_CC") (pintype "passive"))
      (node (ref "R35") (pin "2") (pinfunction "2_2") (pintype "passive"))
    )
    (net (code "123") (name "Net-(LEDJ-PadCC)") (class "Default")
      (node (ref "LEDJ") (pin "CC") (pinfunction "CC_CC") (pintype "passive"))
      (node (ref "R9") (pin "2") (pinfunction "2_2") (pintype "passive"))
    )
    (net (code "124") (name "Net-(NOT_GATEA-O)") (class "Default")
      (node (ref "NOT_GATE") (pin "2") (pinfunction "O_2") (pintype "output"))
      (node (ref "RAM-62256P") (pin "20") (pinfunction "~{CS}_20") (pintype "input"))
    )
    (net (code "125") (name "Net-(NOT_GATEB-O)") (class "Default")
      (node (ref "NOT_GATE") (pin "4") (pinfunction "O_4") (pintype "output"))
      (node (ref "OR_GATE") (pin "12") (pinfunction "A_12") (pintype "input"))
    )
    (net (code "126") (name "Net-(NOT_GATEC-O)") (class "Default")
      (node (ref "NOT_GATE") (pin "6") (pinfunction "O_6") (pintype "output"))
      (node (ref "OR_GATE") (pin "4") (pinfunction "A_4") (pintype "input"))
    )
    (net (code "127") (name "Net-(NOT_GATED-O)") (class "Default")
      (node (ref "NOT_GATE") (pin "8") (pinfunction "O_8") (pintype "output"))
      (node (ref "OR_GATE") (pin "5") (pinfunction "B_5") (pintype "input"))
    )
    (net (code "128") (name "Net-(OR_GATED-Y)") (class "Default")
      (node (ref "OR_GATE") (pin "6") (pinfunction "Y_6") (pintype "output"))
      (node (ref "PORTS-82C55A1") (pin "6") (pinfunction "CS_6") (pintype "input"))
    )
    (net (code "129") (name "Net-(OR_GATEF-Y)") (class "Default")
      (node (ref "OR_GATE") (pin "11") (pinfunction "Y_11") (pintype "output"))
      (node (ref "PORTS-82C55A2") (pin "6") (pinfunction "CS_6") (pintype "input"))
    )
    (net (code "130") (name "VCC") (class "Default")
      (node (ref "ADD_LATCH") (pin "20") (pinfunction "VCC_20") (pintype "power_in"))
      (node (ref "C1") (pin "1") (pinfunction "1_1") (pintype "passive"))
      (node (ref "C10") (pin "1") (pinfunction "1_1") (pintype "passive"))
      (node (ref "C11") (pin "1") (pinfunction "1_1") (pintype "passive"))
      (node (ref "C12") (pin "1") (pinfunction "1_1") (pintype "passive"))
      (node (ref "C13") (pin "1") (pinfunction "1_1") (pintype "passive"))
      (node (ref "C14") (pin "1") (pinfunction "1_1") (pintype "passive"))
      (node (ref "C17") (pin "1") (pinfunction "1_1") (pintype "passive"))
      (node (ref "C2") (pin "1") (pinfunction "1_1") (pintype "passive"))
      (node (ref "C4") (pin "+") (pinfunction "+_+") (pintype "passive"))
      (node (ref "C5") (pin "1") (pinfunction "1_1") (pintype "passive"))
      (node (ref "C6") (pin "1") (pinfunction "1_1") (pintype "passive"))
      (node (ref "C7") (pin "1") (pinfunction "1_1") (pintype "passive"))
      (node (ref "C8") (pin "1") (pinfunction "1_1") (pintype "passive"))
      (node (ref "C9") (pin "1") (pinfunction "1_1") (pintype "passive"))
      (node (ref "IC1") (pin "40") (pinfunction "VCC_40") (pintype "power_in"))
      (node (ref "IC6") (pin "9") (pinfunction "VS_9") (pintype "passive"))
      (node (ref "IC7") (pin "9") (pinfunction "VS_9") (pintype "passive"))
      (node (ref "IC8") (pin "9") (pinfunction "VS_9") (pintype "passive"))
      (node (ref "LCD1") (pin "15") (pinfunction "A_15") (pintype "bidirectional"))
      (node (ref "LCD1") (pin "2") (pinfunction "V+_2") (pintype "bidirectional"))
      (node (ref "NOT_GATE") (pin "14") (pinfunction "VCC_14") (pintype "power_in"))
      (node (ref "OR_GATE") (pin "14") (pinfunction "+UB_14") (pintype "power_in"))
      (node (ref "PORTS-82C55A1") (pin "26") (pinfunction "VCC_26") (pintype "power_in"))
      (node (ref "PORTS-82C55A2") (pin "26") (pinfunction "VCC_26") (pintype "power_in"))
      (node (ref "R10") (pin "2") (pinfunction "2_2") (pintype "passive"))
      (node (ref "R11") (pin "2") (pinfunction "2_2") (pintype "passive"))
      (node (ref "R7") (pin "2") (pinfunction "2_2") (pintype "passive"))
      (node (ref "R8") (pin "1") (pinfunction "1_1") (pintype "passive"))
      (node (ref "RAM-62256P") (pin "28") (pinfunction "VCC_28") (pintype "power_in"))
      (node (ref "ROM-58C256") (pin "27") (pinfunction "~{WE}_27") (pintype "input"))
      (node (ref "ROM-58C256") (pin "28") (pinfunction "VCC_28") (pintype "power_in"))
      (node (ref "U$2") (pin "P$1") (pinfunction "1_P$1") (pintype "passive"))
      (node (ref "X1") (pin "VBUS") (pinfunction "VBUS_VBUS") (pintype "bidirectional"))
    )
    (net (code "131") (name "unconnected-(IC1-CLK-Pad37)") (class "Default")
      (node (ref "IC1") (pin "37") (pinfunction "CLK_37") (pintype "output"))
    )
    (net (code "132") (name "unconnected-(IC1-HLDA-Pad38)") (class "Default")
      (node (ref "IC1") (pin "38") (pinfunction "HLDA_38") (pintype "output"))
    )
    (net (code "133") (name "unconnected-(IC1-INTA-Pad11)") (class "Default")
      (node (ref "IC1") (pin "11") (pinfunction "INTA_11") (pintype "output"))
    )
    (net (code "134") (name "unconnected-(IC1-S0-Pad29)") (class "Default")
      (node (ref "IC1") (pin "29") (pinfunction "S0_29") (pintype "output"))
    )
    (net (code "135") (name "unconnected-(IC1-S1-Pad33)") (class "Default")
      (node (ref "IC1") (pin "33") (pinfunction "S1_33") (pintype "output"))
    )
    (net (code "136") (name "unconnected-(IC8-O8-Pad11)") (class "Default")
      (node (ref "IC8") (pin "11") (pinfunction "O8_11") (pintype "open_collector"))
    )
    (net (code "137") (name "unconnected-(PORTS-82C55A1-PC0-Pad14)") (class "Default")
      (node (ref "PORTS-82C55A1") (pin "14") (pinfunction "PC0_14") (pintype "bidirectional"))
    )
    (net (code "138") (name "unconnected-(PORTS-82C55A1-PC1-Pad15)") (class "Default")
      (node (ref "PORTS-82C55A1") (pin "15") (pinfunction "PC1_15") (pintype "bidirectional"))
    )
    (net (code "139") (name "unconnected-(PORTS-82C55A1-PC2-Pad16)") (class "Default")
      (node (ref "PORTS-82C55A1") (pin "16") (pinfunction "PC2_16") (pintype "bidirectional"))
    )
    (net (code "140") (name "unconnected-(PORTS-82C55A1-PC3-Pad17)") (class "Default")
      (node (ref "PORTS-82C55A1") (pin "17") (pinfunction "PC3_17") (pintype "bidirectional"))
    )
    (net (code "141") (name "unconnected-(PORTS-82C55A1-PC7-Pad10)") (class "Default")
      (node (ref "PORTS-82C55A1") (pin "10") (pinfunction "PC7_10") (pintype "bidirectional"))
    )
    (net (code "142") (name "unconnected-(X1-PadD+)") (class "Default")
      (node (ref "X1") (pin "D+") (pinfunction "D+_D+") (pintype "bidirectional"))
    )
    (net (code "143") (name "unconnected-(X1-PadD-)") (class "Default")
      (node (ref "X1") (pin "D-") (pinfunction "D-_D-") (pintype "bidirectional"))
    )
  )
)
